# BStream_Upcycled.net
KiCad netlist of a schematic drawn in EAGLE
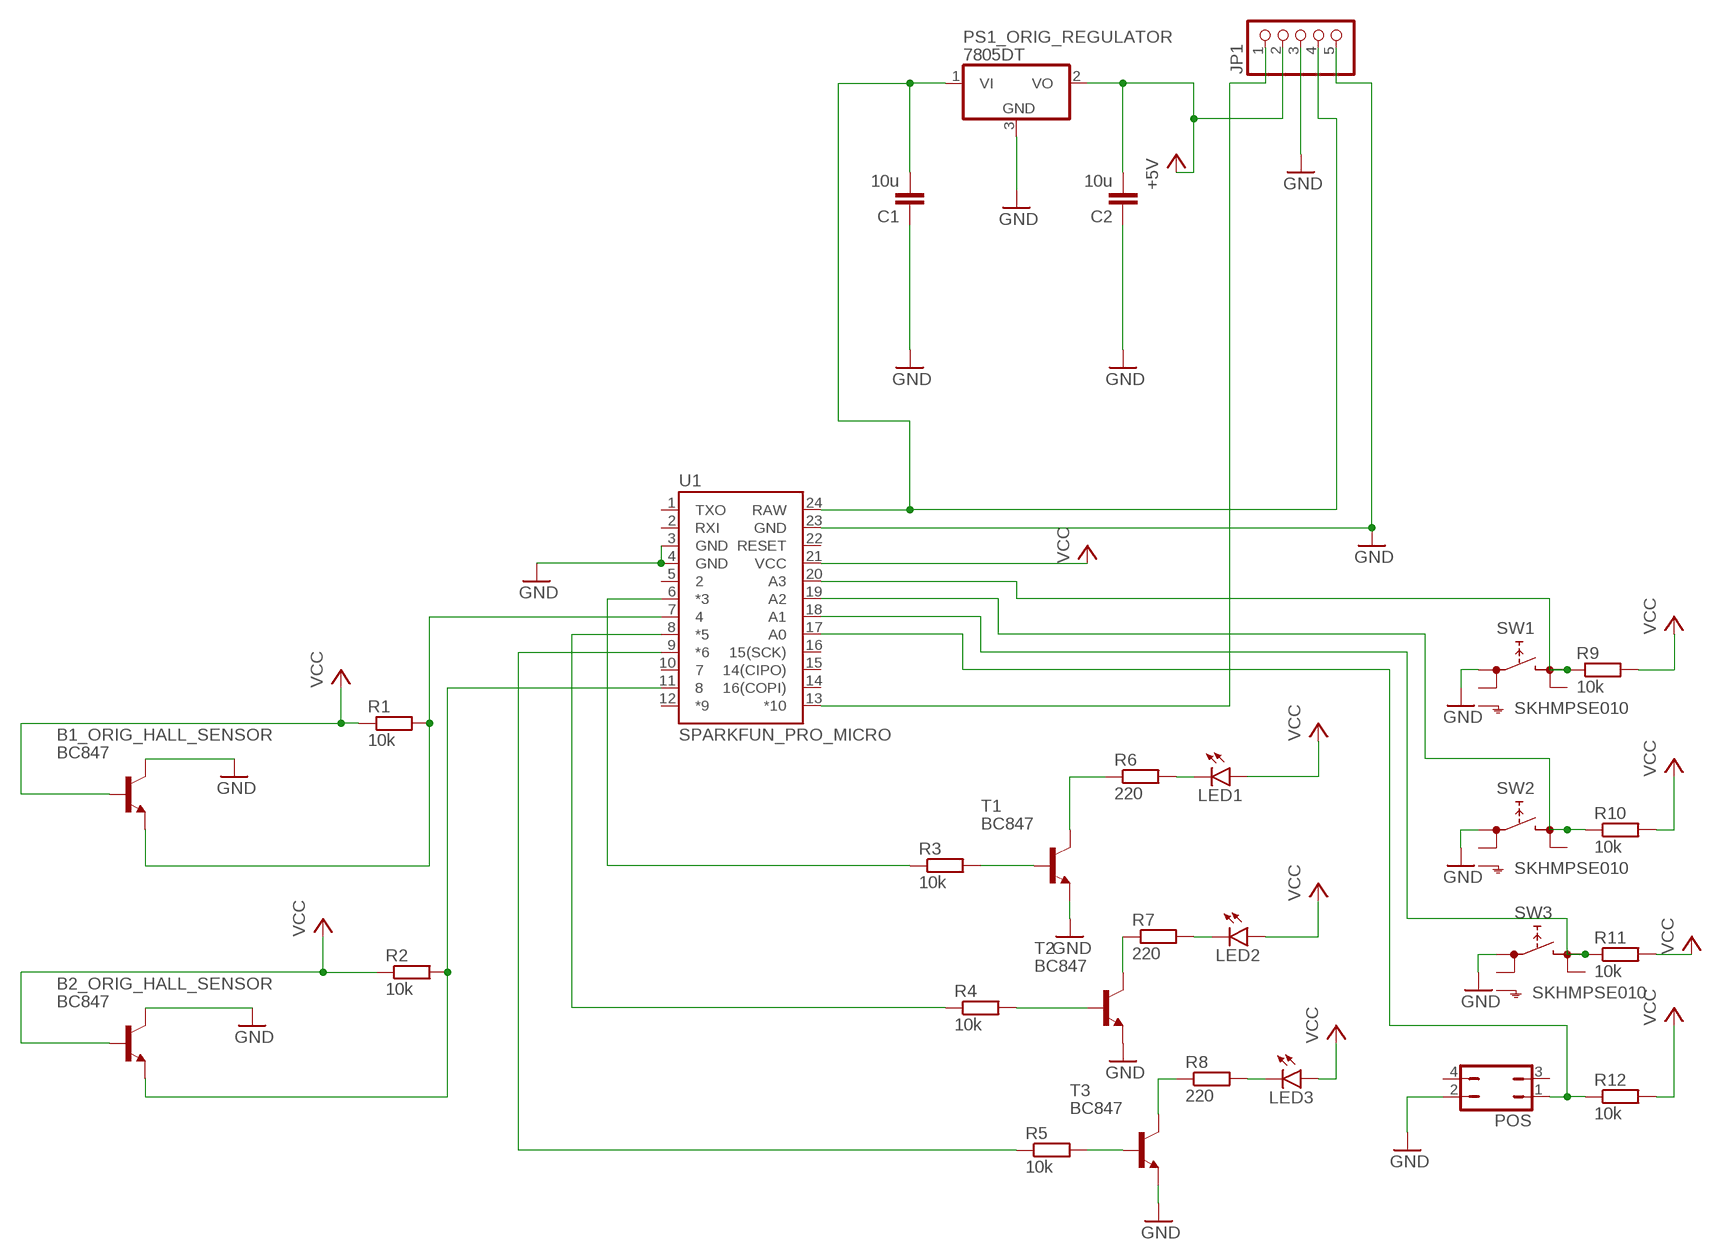
[diagram p0: schematic, sheet 1]

(export (version "E")
  (design (tool "Eeschema 10.0.6"))
  (components
    (comp (ref "B1_ORIG_HALL_SENSOR")
      (value "BC847")
      (footprint "eagle-import:SOT23")
      (libsource (lib "eagle-import") (part "BC847"))
    )
    (comp (ref "B2_ORIG_HALL_SENSOR")
      (value "BC847")
      (footprint "eagle-import:SOT23")
      (libsource (lib "eagle-import") (part "BC847"))
    )
    (comp (ref "C1")
      (value "10u")
      (footprint "eagle-import:C1206")
      (libsource (lib "eagle-import") (part "C-EUC1206"))
    )
    (comp (ref "C2")
      (value "10u")
      (footprint "eagle-import:C1206")
      (libsource (lib "eagle-import") (part "C-EUC1206"))
    )
    (comp (ref "JP1")
      (value "PINHD-1X5")
      (footprint "eagle-import:1X05")
      (libsource (lib "eagle-import") (part "PINHD-1X5"))
    )
    (comp (ref "LED1")
      (value "LEDSML1206")
      (footprint "eagle-import:SML1206")
      (libsource (lib "eagle-import") (part "LEDSML1206"))
    )
    (comp (ref "LED2")
      (value "LEDSML1206")
      (footprint "eagle-import:SML1206")
      (libsource (lib "eagle-import") (part "LEDSML1206"))
    )
    (comp (ref "LED3")
      (value "LEDSML1206")
      (footprint "eagle-import:SML1206")
      (libsource (lib "eagle-import") (part "LEDSML1206"))
    )
    (comp (ref "POS")
      (value "JP2Q")
      (footprint "eagle-import:JP2Q")
      (libsource (lib "eagle-import") (part "JP2Q"))
    )
    (comp (ref "PS1_ORIG_REGULATOR")
      (value "7805DT")
      (footprint "eagle-import:TO252")
      (libsource (lib "eagle-import") (part "78DT05"))
    )
    (comp (ref "R1")
      (value "10k")
      (footprint "eagle-import:R1206")
      (libsource (lib "eagle-import") (part "R-EU_R1206"))
    )
    (comp (ref "R2")
      (value "10k")
      (footprint "eagle-import:R1206")
      (libsource (lib "eagle-import") (part "R-EU_R1206"))
    )
    (comp (ref "R3")
      (value "10k")
      (footprint "eagle-import:R1206")
      (libsource (lib "eagle-import") (part "R-EU_R1206"))
    )
    (comp (ref "R4")
      (value "10k")
      (footprint "eagle-import:R1206")
      (libsource (lib "eagle-import") (part "R-EU_R1206"))
    )
    (comp (ref "R5")
      (value "10k")
      (footprint "eagle-import:R1206")
      (libsource (lib "eagle-import") (part "R-EU_R1206"))
    )
    (comp (ref "R6")
      (value "220")
      (footprint "eagle-import:R1206")
      (libsource (lib "eagle-import") (part "R-EU_R1206"))
    )
    (comp (ref "R7")
      (value "220")
      (footprint "eagle-import:R1206")
      (libsource (lib "eagle-import") (part "R-EU_R1206"))
    )
    (comp (ref "R8")
      (value "220")
      (footprint "eagle-import:R1206")
      (libsource (lib "eagle-import") (part "R-EU_R1206"))
    )
    (comp (ref "R9")
      (value "10k")
      (footprint "eagle-import:R1206")
      (libsource (lib "eagle-import") (part "R-EU_R1206"))
    )
    (comp (ref "R10")
      (value "10k")
      (footprint "eagle-import:R1206")
      (libsource (lib "eagle-import") (part "R-EU_R1206"))
    )
    (comp (ref "R11")
      (value "10k")
      (footprint "eagle-import:R1206")
      (libsource (lib "eagle-import") (part "R-EU_R1206"))
    )
    (comp (ref "R12")
      (value "10k")
      (footprint "eagle-import:R1206")
      (libsource (lib "eagle-import") (part "R-EU_R1206"))
    )
    (comp (ref "SW1")
      (value "SKHMPSE010")
      (footprint "eagle-import:SKHMPXE010")
      (libsource (lib "eagle-import") (part "SKHMPE010S"))
    )
    (comp (ref "SW2")
      (value "SKHMPSE010")
      (footprint "eagle-import:SKHMPXE010")
      (libsource (lib "eagle-import") (part "SKHMPE010S"))
    )
    (comp (ref "SW3")
      (value "SKHMPSE010")
      (footprint "eagle-import:SKHMPXE010")
      (libsource (lib "eagle-import") (part "SKHMPE010S"))
    )
    (comp (ref "T1")
      (value "BC847")
      (footprint "eagle-import:SOT23")
      (libsource (lib "eagle-import") (part "BC847"))
    )
    (comp (ref "T2")
      (value "BC847")
      (footprint "eagle-import:SOT23")
      (libsource (lib "eagle-import") (part "BC847"))
    )
    (comp (ref "T3")
      (value "BC847")
      (footprint "eagle-import:SOT23")
      (libsource (lib "eagle-import") (part "BC847"))
    )
    (comp (ref "U1")
      (value "SPARKFUN_PRO_MICRO")
      (footprint "eagle-import:SPARKFUN_PRO_MICRO")
      (libsource (lib "eagle-import") (part "SPARKFUN_PRO_MICRO"))
    )
  )
  (nets
    (net (code "1") (name "+5V") (class "Default")
      (node (ref "C2") (pin "2") (pinfunction "2_2") (pintype "passive"))
      (node (ref "JP1") (pin "2") (pinfunction "2_2") (pintype "passive"))
      (node (ref "PS1_ORIG_REGULATOR") (pin "2") (pinfunction "VO_2") (pintype "passive"))
    )
    (net (code "2") (name "GND") (class "Default")
      (node (ref "B1_ORIG_HALL_SENSOR") (pin "3") (pinfunction "C_3") (pintype "passive"))
      (node (ref "B2_ORIG_HALL_SENSOR") (pin "3") (pinfunction "C_3") (pintype "passive"))
      (node (ref "C1") (pin "1") (pinfunction "1_1") (pintype "passive"))
      (node (ref "C2") (pin "1") (pinfunction "1_1") (pintype "passive"))
      (node (ref "JP1") (pin "3") (pinfunction "3_3") (pintype "passive"))
      (node (ref "JP1") (pin "5") (pinfunction "5_5") (pintype "passive"))
      (node (ref "POS") (pin "2") (pinfunction "2_2") (pintype "passive"))
      (node (ref "PS1_ORIG_REGULATOR") (pin "3") (pinfunction "GND_3") (pintype "passive"))
      (node (ref "SW1") (pin "1") (pinfunction "1.1_1") (pintype "passive"))
      (node (ref "SW2") (pin "1") (pinfunction "1.1_1") (pintype "passive"))
      (node (ref "SW3") (pin "1") (pinfunction "1.1_1") (pintype "passive"))
      (node (ref "T1") (pin "2") (pinfunction "E_2") (pintype "passive"))
      (node (ref "T2") (pin "2") (pinfunction "E_2") (pintype "passive"))
      (node (ref "T3") (pin "2") (pinfunction "E_2") (pintype "passive"))
      (node (ref "U1") (pin "23") (pinfunction "GND_23") (pintype "power_in"))
      (node (ref "U1") (pin "3") (pinfunction "GND_3") (pintype "power_in"))
      (node (ref "U1") (pin "4") (pinfunction "GND_4") (pintype "power_in"))
    )
    (net (code "3") (name "Net-(B1_ORIG_HALL_SENSOR-E)") (class "Default")
      (node (ref "B1_ORIG_HALL_SENSOR") (pin "2") (pinfunction "E_2") (pintype "passive"))
      (node (ref "R1") (pin "2") (pinfunction "2_2") (pintype "passive"))
      (node (ref "U1") (pin "7") (pinfunction "4_7") (pintype "bidirectional"))
    )
    (net (code "4") (name "Net-(B2_ORIG_HALL_SENSOR-E)") (class "Default")
      (node (ref "B2_ORIG_HALL_SENSOR") (pin "2") (pinfunction "E_2") (pintype "passive"))
      (node (ref "R2") (pin "2") (pinfunction "2_2") (pintype "passive"))
      (node (ref "U1") (pin "11") (pinfunction "8_11") (pintype "bidirectional"))
    )
    (net (code "5") (name "Net-(LED1-PadC)") (class "Default")
      (node (ref "LED1") (pin "C") (pinfunction "C_C") (pintype "passive"))
      (node (ref "R6") (pin "2") (pinfunction "2_2") (pintype "passive"))
    )
    (net (code "6") (name "Net-(LED2-PadC)") (class "Default")
      (node (ref "LED2") (pin "C") (pinfunction "C_C") (pintype "passive"))
      (node (ref "R7") (pin "2") (pinfunction "2_2") (pintype "passive"))
    )
    (net (code "7") (name "Net-(LED3-PadC)") (class "Default")
      (node (ref "LED3") (pin "C") (pinfunction "C_C") (pintype "passive"))
      (node (ref "R8") (pin "2") (pinfunction "2_2") (pintype "passive"))
    )
    (net (code "8") (name "Net-(PS1_ORIG_REGULATOR-VI)") (class "Default")
      (node (ref "C1") (pin "2") (pinfunction "2_2") (pintype "passive"))
      (node (ref "JP1") (pin "4") (pinfunction "4_4") (pintype "passive"))
      (node (ref "PS1_ORIG_REGULATOR") (pin "1") (pinfunction "VI_1") (pintype "input"))
      (node (ref "U1") (pin "24") (pinfunction "RAW_24") (pintype "power_in"))
    )
    (net (code "9") (name "Net-(SW1-2.1)") (class "Default")
      (node (ref "R9") (pin "1") (pinfunction "1_1") (pintype "passive"))
      (node (ref "SW1") (pin "3") (pinfunction "2.1_3") (pintype "passive"))
      (node (ref "U1") (pin "20") (pinfunction "A3_20") (pintype "bidirectional"))
    )
    (net (code "10") (name "Net-(SW2-2.1)") (class "Default")
      (node (ref "R10") (pin "1") (pinfunction "1_1") (pintype "passive"))
      (node (ref "SW2") (pin "3") (pinfunction "2.1_3") (pintype "passive"))
      (node (ref "U1") (pin "19") (pinfunction "A2_19") (pintype "bidirectional"))
    )
    (net (code "11") (name "Net-(SW3-2.1)") (class "Default")
      (node (ref "R11") (pin "1") (pinfunction "1_1") (pintype "passive"))
      (node (ref "SW3") (pin "3") (pinfunction "2.1_3") (pintype "passive"))
      (node (ref "U1") (pin "18") (pinfunction "A1_18") (pintype "bidirectional"))
    )
    (net (code "12") (name "Net-(T1-B)") (class "Default")
      (node (ref "R3") (pin "2") (pinfunction "2_2") (pintype "passive"))
      (node (ref "T1") (pin "1") (pinfunction "B_1") (pintype "passive"))
    )
    (net (code "13") (name "Net-(T1-C)") (class "Default")
      (node (ref "R6") (pin "1") (pinfunction "1_1") (pintype "passive"))
      (node (ref "T1") (pin "3") (pinfunction "C_3") (pintype "passive"))
    )
    (net (code "14") (name "Net-(T2-B)") (class "Default")
      (node (ref "R4") (pin "2") (pinfunction "2_2") (pintype "passive"))
      (node (ref "T2") (pin "1") (pinfunction "B_1") (pintype "passive"))
    )
    (net (code "15") (name "Net-(T2-C)") (class "Default")
      (node (ref "R7") (pin "1") (pinfunction "1_1") (pintype "passive"))
      (node (ref "T2") (pin "3") (pinfunction "C_3") (pintype "passive"))
    )
    (net (code "16") (name "Net-(T3-B)") (class "Default")
      (node (ref "R5") (pin "2") (pinfunction "2_2") (pintype "passive"))
      (node (ref "T3") (pin "1") (pinfunction "B_1") (pintype "passive"))
    )
    (net (code "17") (name "Net-(T3-C)") (class "Default")
      (node (ref "R8") (pin "1") (pinfunction "1_1") (pintype "passive"))
      (node (ref "T3") (pin "3") (pinfunction "C_3") (pintype "passive"))
    )
    (net (code "18") (name "Net-(U1-*3)") (class "Default")
      (node (ref "R3") (pin "1") (pinfunction "1_1") (pintype "passive"))
      (node (ref "U1") (pin "6") (pinfunction "*3_6") (pintype "bidirectional"))
    )
    (net (code "19") (name "Net-(U1-*5)") (class "Default")
      (node (ref "R4") (pin "1") (pinfunction "1_1") (pintype "passive"))
      (node (ref "U1") (pin "8") (pinfunction "*5_8") (pintype "bidirectional"))
    )
    (net (code "20") (name "Net-(U1-*6)") (class "Default")
      (node (ref "R5") (pin "1") (pinfunction "1_1") (pintype "passive"))
      (node (ref "U1") (pin "9") (pinfunction "*6_9") (pintype "bidirectional"))
    )
    (net (code "21") (name "Net-(U1-*10)") (class "Default")
      (node (ref "JP1") (pin "1") (pinfunction "1_1") (pintype "passive"))
      (node (ref "U1") (pin "13") (pinfunction "*10_13") (pintype "bidirectional"))
    )
    (net (code "22") (name "Net-(U1-A0)") (class "Default")
      (node (ref "POS") (pin "1") (pinfunction "1_1") (pintype "passive"))
      (node (ref "R12") (pin "1") (pinfunction "1_1") (pintype "passive"))
      (node (ref "U1") (pin "17") (pinfunction "A0_17") (pintype "bidirectional"))
    )
    (net (code "23") (name "VCC") (class "Default")
      (node (ref "B1_ORIG_HALL_SENSOR") (pin "1") (pinfunction "B_1") (pintype "passive"))
      (node (ref "B2_ORIG_HALL_SENSOR") (pin "1") (pinfunction "B_1") (pintype "passive"))
      (node (ref "LED1") (pin "A") (pinfunction "A_A") (pintype "passive"))
      (node (ref "LED2") (pin "A") (pinfunction "A_A") (pintype "passive"))
      (node (ref "LED3") (pin "A") (pinfunction "A_A") (pintype "passive"))
      (node (ref "R1") (pin "1") (pinfunction "1_1") (pintype "passive"))
      (node (ref "R10") (pin "2") (pinfunction "2_2") (pintype "passive"))
      (node (ref "R11") (pin "2") (pinfunction "2_2") (pintype "passive"))
      (node (ref "R12") (pin "2") (pinfunction "2_2") (pintype "passive"))
      (node (ref "R2") (pin "1") (pinfunction "1_1") (pintype "passive"))
      (node (ref "R9") (pin "2") (pinfunction "2_2") (pintype "passive"))
      (node (ref "U1") (pin "21") (pinfunction "VCC_21") (pintype "power_in"))
    )
    (net (code "24") (name "unconnected-(POS-Pad3)") (class "Default")
      (node (ref "POS") (pin "3") (pinfunction "3_3") (pintype "passive"))
    )
    (net (code "25") (name "unconnected-(POS-Pad4)") (class "Default")
      (node (ref "POS") (pin "4") (pinfunction "4_4") (pintype "passive"))
    )
    (net (code "26") (name "unconnected-(SW1-1.2-Pad2)") (class "Default")
      (node (ref "SW1") (pin "2") (pinfunction "1.2_2") (pintype "passive"))
    )
    (net (code "27") (name "unconnected-(SW1-2.2-Pad4)") (class "Default")
      (node (ref "SW1") (pin "4") (pinfunction "2.2_4") (pintype "passive"))
    )
    (net (code "28") (name "unconnected-(SW1-SH-Pad5)") (class "Default")
      (node (ref "SW1") (pin "5") (pinfunction "SH_5") (pintype "passive"))
    )
    (net (code "29") (name "unconnected-(SW2-1.2-Pad2)") (class "Default")
      (node (ref "SW2") (pin "2") (pinfunction "1.2_2") (pintype "passive"))
    )
    (net (code "30") (name "unconnected-(SW2-2.2-Pad4)") (class "Default")
      (node (ref "SW2") (pin "4") (pinfunction "2.2_4") (pintype "passive"))
    )
    (net (code "31") (name "unconnected-(SW2-SH-Pad5)") (class "Default")
      (node (ref "SW2") (pin "5") (pinfunction "SH_5") (pintype "passive"))
    )
    (net (code "32") (name "unconnected-(SW3-1.2-Pad2)") (class "Default")
      (node (ref "SW3") (pin "2") (pinfunction "1.2_2") (pintype "passive"))
    )
    (net (code "33") (name "unconnected-(SW3-2.2-Pad4)") (class "Default")
      (node (ref "SW3") (pin "4") (pinfunction "2.2_4") (pintype "passive"))
    )
    (net (code "34") (name "unconnected-(SW3-SH-Pad5)") (class "Default")
      (node (ref "SW3") (pin "5") (pinfunction "SH_5") (pintype "passive"))
    )
    (net (code "35") (name "unconnected-(U1-*9-Pad12)") (class "Default")
      (node (ref "U1") (pin "12") (pinfunction "*9_12") (pintype "bidirectional"))
    )
    (net (code "36") (name "unconnected-(U1-2-Pad5)") (class "Default")
      (node (ref "U1") (pin "5") (pinfunction "2_5") (pintype "bidirectional"))
    )
    (net (code "37") (name "unconnected-(U1-7-Pad10)") (class "Default")
      (node (ref "U1") (pin "10") (pinfunction "7_10") (pintype "bidirectional"))
    )
    (net (code "38") (name "unconnected-(U1-14(CIPO)-Pad15)") (class "Default")
      (node (ref "U1") (pin "15") (pinfunction "14(CIPO)_15") (pintype "bidirectional"))
    )
    (net (code "39") (name "unconnected-(U1-15(SCK)-Pad16)") (class "Default")
      (node (ref "U1") (pin "16") (pinfunction "15(SCK)_16") (pintype "bidirectional"))
    )
    (net (code "40") (name "unconnected-(U1-16(COPI)-Pad14)") (class "Default")
      (node (ref "U1") (pin "14") (pinfunction "16(COPI)_14") (pintype "bidirectional"))
    )
    (net (code "41") (name "unconnected-(U1-RESET-Pad22)") (class "Default")
      (node (ref "U1") (pin "22") (pinfunction "RESET_22") (pintype "bidirectional"))
    )
    (net (code "42") (name "unconnected-(U1-RXI-Pad2)") (class "Default")
      (node (ref "U1") (pin "2") (pinfunction "RXI_2") (pintype "bidirectional"))
    )
    (net (code "43") (name "unconnected-(U1-TXO-Pad1)") (class "Default")
      (node (ref "U1") (pin "1") (pinfunction "TXO_1") (pintype "bidirectional"))
    )
  )
)
